# MODULO0.net
KiCad netlist of a schematic drawn in EAGLE
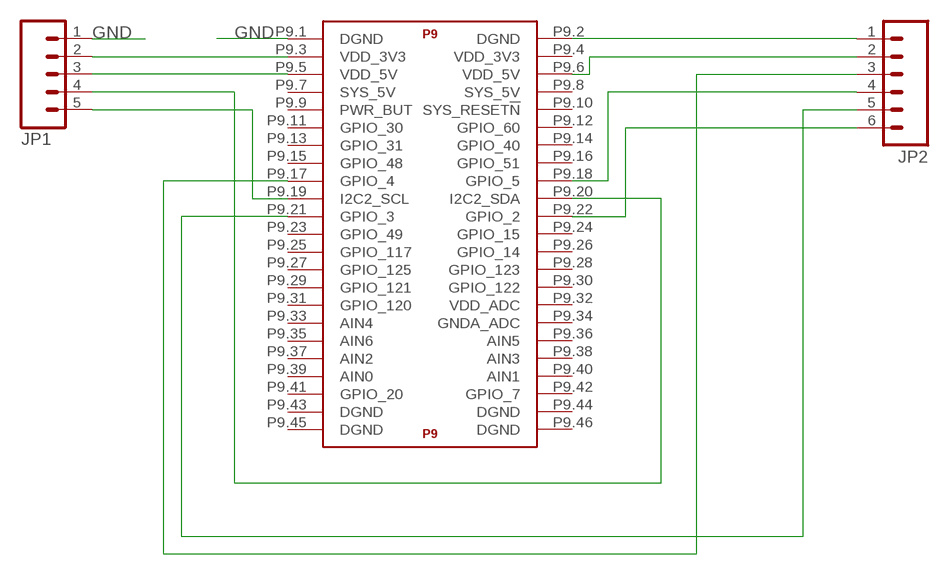
[diagram p0: schematic, sheet 1]

(export (version "E")
  (design (tool "Eeschema 10.0.6"))
  (components
    (comp (ref "JP1")
      (value "M05PTH")
      (footprint "eagle-import:1X05")
      (libsource (lib "eagle-import") (part "M05PTH"))
    )
    (comp (ref "JP2")
      (value "M06SILK_FEMALE_PTH")
      (footprint "eagle-import:1X06")
      (libsource (lib "eagle-import") (part "M06SILK_FEMALE_PTH"))
    )
    (comp (ref "U$1")
      (value "BEAGLE_BONE_BLACK_CAPE")
      (footprint "eagle-import:BEAGLE_BONE_BLACK_CAPE")
      (libsource (lib "eagle-import") (part "BEAGLE_BONE_BLACK_CAPE"))
    )
  )
  (nets
    (net (code "1") (name "/GND") (class "Default")
      (node (ref "JP1") (pin "1") (pinfunction "1_1") (pintype "passive"))
      (node (ref "U$1") (pin "P9.1") (pinfunction "DGND_P9.1") (pintype "bidirectional"))
    )
    (net (code "2") (name "Net-(JP1-Pad2)") (class "Default")
      (node (ref "JP1") (pin "2") (pinfunction "2_2") (pintype "passive"))
      (node (ref "U$1") (pin "P9.3") (pinfunction "VDD_3V3_P9.3") (pintype "bidirectional"))
    )
    (net (code "3") (name "Net-(JP1-Pad3)") (class "Default")
      (node (ref "JP1") (pin "3") (pinfunction "3_3") (pintype "passive"))
      (node (ref "U$1") (pin "P9.5") (pinfunction "VDD_5V_P9.5") (pintype "bidirectional"))
    )
    (net (code "4") (name "Net-(JP2-Pad1)") (class "Default")
      (node (ref "JP2") (pin "1") (pinfunction "1_1") (pintype "passive"))
      (node (ref "U$1") (pin "P9.2") (pinfunction "DGND_P9.2") (pintype "bidirectional"))
    )
    (net (code "5") (name "Net-(JP2-Pad2)") (class "Default")
      (node (ref "JP2") (pin "2") (pinfunction "2_2") (pintype "passive"))
      (node (ref "U$1") (pin "P9.6") (pinfunction "VDD_5V_P9.6") (pintype "bidirectional"))
    )
    (net (code "6") (name "Net-(U$1B-GPIO_2)") (class "Default")
      (node (ref "JP2") (pin "6") (pinfunction "6_6") (pintype "passive"))
      (node (ref "U$1") (pin "P9.22") (pinfunction "GPIO_2_P9.22") (pintype "bidirectional"))
    )
    (net (code "7") (name "Net-(U$1B-GPIO_3)") (class "Default")
      (node (ref "JP2") (pin "5") (pinfunction "5_5") (pintype "passive"))
      (node (ref "U$1") (pin "P9.21") (pinfunction "GPIO_3_P9.21") (pintype "bidirectional"))
    )
    (net (code "8") (name "Net-(U$1B-GPIO_4)") (class "Default")
      (node (ref "JP2") (pin "3") (pinfunction "3_3") (pintype "passive"))
      (node (ref "U$1") (pin "P9.17") (pinfunction "GPIO_4_P9.17") (pintype "bidirectional"))
    )
    (net (code "9") (name "Net-(U$1B-GPIO_5)") (class "Default")
      (node (ref "JP2") (pin "4") (pinfunction "4_4") (pintype "passive"))
      (node (ref "U$1") (pin "P9.18") (pinfunction "GPIO_5_P9.18") (pintype "bidirectional"))
    )
    (net (code "10") (name "Net-(U$1B-I2C2_SCL)") (class "Default")
      (node (ref "JP1") (pin "5") (pinfunction "5_5") (pintype "passive"))
      (node (ref "U$1") (pin "P9.19") (pinfunction "I2C2_SCL_P9.19") (pintype "bidirectional"))
    )
    (net (code "11") (name "Net-(U$1B-I2C2_SDA)") (class "Default")
      (node (ref "JP1") (pin "4") (pinfunction "4_4") (pintype "passive"))
      (node (ref "U$1") (pin "P9.20") (pinfunction "I2C2_SDA_P9.20") (pintype "bidirectional"))
    )
    (net (code "12") (name "unconnected-(U$1B-AIN0-PadP9.39)") (class "Default")
      (node (ref "U$1") (pin "P9.39") (pinfunction "AIN0_P9.39") (pintype "bidirectional"))
    )
    (net (code "13") (name "unconnected-(U$1B-AIN1-PadP9.40)") (class "Default")
      (node (ref "U$1") (pin "P9.40") (pinfunction "AIN1_P9.40") (pintype "bidirectional"))
    )
    (net (code "14") (name "unconnected-(U$1B-AIN2-PadP9.37)") (class "Default")
      (node (ref "U$1") (pin "P9.37") (pinfunction "AIN2_P9.37") (pintype "bidirectional"))
    )
    (net (code "15") (name "unconnected-(U$1B-AIN3-PadP9.38)") (class "Default")
      (node (ref "U$1") (pin "P9.38") (pinfunction "AIN3_P9.38") (pintype "bidirectional"))
    )
    (net (code "16") (name "unconnected-(U$1B-AIN4-PadP9.33)") (class "Default")
      (node (ref "U$1") (pin "P9.33") (pinfunction "AIN4_P9.33") (pintype "bidirectional"))
    )
    (net (code "17") (name "unconnected-(U$1B-AIN5-PadP9.36)") (class "Default")
      (node (ref "U$1") (pin "P9.36") (pinfunction "AIN5_P9.36") (pintype "bidirectional"))
    )
    (net (code "18") (name "unconnected-(U$1B-AIN6-PadP9.35)") (class "Default")
      (node (ref "U$1") (pin "P9.35") (pinfunction "AIN6_P9.35") (pintype "bidirectional"))
    )
    (net (code "19") (name "unconnected-(U$1B-DGND-PadP9.43)") (class "Default")
      (node (ref "U$1") (pin "P9.43") (pinfunction "DGND_P9.43") (pintype "bidirectional"))
    )
    (net (code "20") (name "unconnected-(U$1B-DGND-PadP9.44)") (class "Default")
      (node (ref "U$1") (pin "P9.44") (pinfunction "DGND_P9.44") (pintype "bidirectional"))
    )
    (net (code "21") (name "unconnected-(U$1B-DGND-PadP9.45)") (class "Default")
      (node (ref "U$1") (pin "P9.45") (pinfunction "DGND_P9.45") (pintype "bidirectional"))
    )
    (net (code "22") (name "unconnected-(U$1B-DGND-PadP9.46)") (class "Default")
      (node (ref "U$1") (pin "P9.46") (pinfunction "DGND_P9.46") (pintype "bidirectional"))
    )
    (net (code "23") (name "unconnected-(U$1B-GNDA_ADC-PadP9.34)") (class "Default")
      (node (ref "U$1") (pin "P9.34") (pinfunction "GNDA_ADC_P9.34") (pintype "bidirectional"))
    )
    (net (code "24") (name "unconnected-(U$1B-GPIO_7-PadP9.42)") (class "Default")
      (node (ref "U$1") (pin "P9.42") (pinfunction "GPIO_7_P9.42") (pintype "bidirectional"))
    )
    (net (code "25") (name "unconnected-(U$1B-GPIO_14-PadP9.26)") (class "Default")
      (node (ref "U$1") (pin "P9.26") (pinfunction "GPIO_14_P9.26") (pintype "bidirectional"))
    )
    (net (code "26") (name "unconnected-(U$1B-GPIO_15-PadP9.24)") (class "Default")
      (node (ref "U$1") (pin "P9.24") (pinfunction "GPIO_15_P9.24") (pintype "bidirectional"))
    )
    (net (code "27") (name "unconnected-(U$1B-GPIO_20-PadP9.41)") (class "Default")
      (node (ref "U$1") (pin "P9.41") (pinfunction "GPIO_20_P9.41") (pintype "bidirectional"))
    )
    (net (code "28") (name "unconnected-(U$1B-GPIO_30-PadP9.11)") (class "Default")
      (node (ref "U$1") (pin "P9.11") (pinfunction "GPIO_30_P9.11") (pintype "bidirectional"))
    )
    (net (code "29") (name "unconnected-(U$1B-GPIO_31-PadP9.13)") (class "Default")
      (node (ref "U$1") (pin "P9.13") (pinfunction "GPIO_31_P9.13") (pintype "bidirectional"))
    )
    (net (code "30") (name "unconnected-(U$1B-GPIO_40-PadP9.14)") (class "Default")
      (node (ref "U$1") (pin "P9.14") (pinfunction "GPIO_40_P9.14") (pintype "bidirectional"))
    )
    (net (code "31") (name "unconnected-(U$1B-GPIO_48-PadP9.15)") (class "Default")
      (node (ref "U$1") (pin "P9.15") (pinfunction "GPIO_48_P9.15") (pintype "bidirectional"))
    )
    (net (code "32") (name "unconnected-(U$1B-GPIO_49-PadP9.23)") (class "Default")
      (node (ref "U$1") (pin "P9.23") (pinfunction "GPIO_49_P9.23") (pintype "bidirectional"))
    )
    (net (code "33") (name "unconnected-(U$1B-GPIO_51-PadP9.16)") (class "Default")
      (node (ref "U$1") (pin "P9.16") (pinfunction "GPIO_51_P9.16") (pintype "bidirectional"))
    )
    (net (code "34") (name "unconnected-(U$1B-GPIO_60-PadP9.12)") (class "Default")
      (node (ref "U$1") (pin "P9.12") (pinfunction "GPIO_60_P9.12") (pintype "bidirectional"))
    )
    (net (code "35") (name "unconnected-(U$1B-GPIO_117-PadP9.25)") (class "Default")
      (node (ref "U$1") (pin "P9.25") (pinfunction "GPIO_117_P9.25") (pintype "bidirectional"))
    )
    (net (code "36") (name "unconnected-(U$1B-GPIO_120-PadP9.31)") (class "Default")
      (node (ref "U$1") (pin "P9.31") (pinfunction "GPIO_120_P9.31") (pintype "bidirectional"))
    )
    (net (code "37") (name "unconnected-(U$1B-GPIO_121-PadP9.29)") (class "Default")
      (node (ref "U$1") (pin "P9.29") (pinfunction "GPIO_121_P9.29") (pintype "bidirectional"))
    )
    (net (code "38") (name "unconnected-(U$1B-GPIO_122-PadP9.30)") (class "Default")
      (node (ref "U$1") (pin "P9.30") (pinfunction "GPIO_122_P9.30") (pintype "bidirectional"))
    )
    (net (code "39") (name "unconnected-(U$1B-GPIO_123-PadP9.28)") (class "Default")
      (node (ref "U$1") (pin "P9.28") (pinfunction "GPIO_123_P9.28") (pintype "bidirectional"))
    )
    (net (code "40") (name "unconnected-(U$1B-GPIO_125-PadP9.27)") (class "Default")
      (node (ref "U$1") (pin "P9.27") (pinfunction "GPIO_125_P9.27") (pintype "bidirectional"))
    )
    (net (code "41") (name "unconnected-(U$1B-PWR_BUT-PadP9.9)") (class "Default")
      (node (ref "U$1") (pin "P9.9") (pinfunction "PWR_BUT_P9.9") (pintype "bidirectional"))
    )
    (net (code "42") (name "unconnected-(U$1B-SYS_5V-PadP9.7)") (class "Default")
      (node (ref "U$1") (pin "P9.7") (pinfunction "SYS_5V_P9.7") (pintype "bidirectional"))
    )
    (net (code "43") (name "unconnected-(U$1B-SYS_5V-PadP9.8)") (class "Default")
      (node (ref "U$1") (pin "P9.8") (pinfunction "SYS_5V_P9.8") (pintype "bidirectional"))
    )
    (net (code "44") (name "unconnected-(U$1B-SYS_RESET~{N}-PadP9.10)") (class "Default")
      (node (ref "U$1") (pin "P9.10") (pinfunction "SYS_RESET~{N}_P9.10") (pintype "bidirectional"))
    )
    (net (code "45") (name "unconnected-(U$1B-VDD_3V3-PadP9.4)") (class "Default")
      (node (ref "U$1") (pin "P9.4") (pinfunction "VDD_3V3_P9.4") (pintype "bidirectional"))
    )
    (net (code "46") (name "unconnected-(U$1B-VDD_ADC-PadP9.32)") (class "Default")
      (node (ref "U$1") (pin "P9.32") (pinfunction "VDD_ADC_P9.32") (pintype "bidirectional"))
    )
  )
)
